# Servo_module.net
KiCad netlist of a schematic drawn in EasyEDA Pro
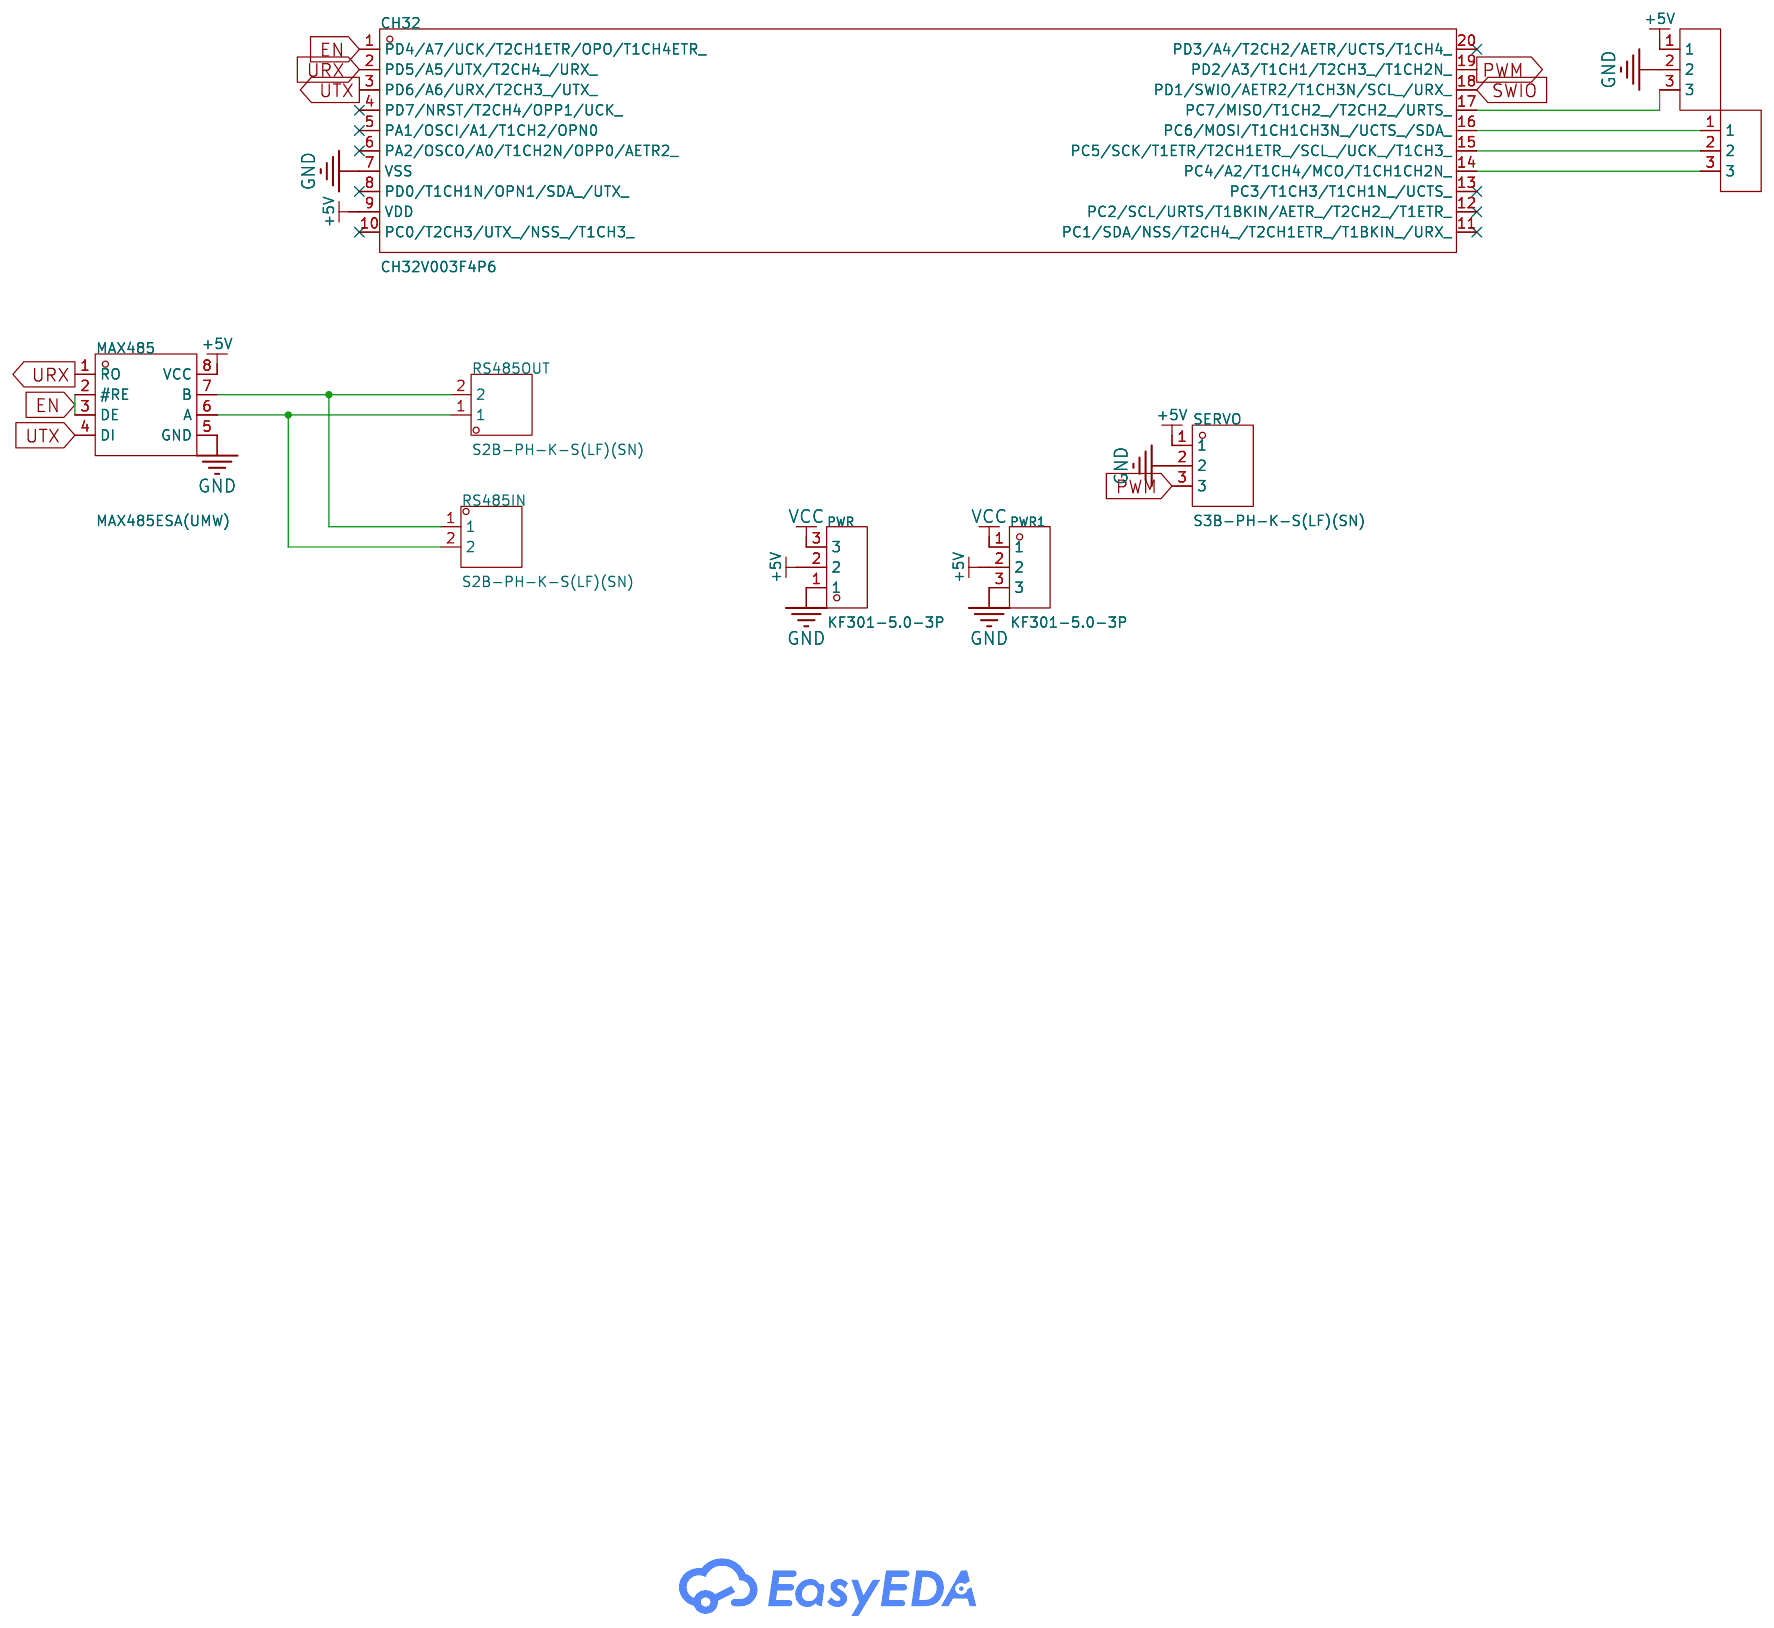
[diagram p0: schematic sheet]

(export (version "E")
  (design (tool "Eeschema 10.0.6"))
  (components
    (comp (ref "CH32")
      (value "CH32V003F4P6")
      (footprint "easyedapro:TSSOP-20_L6.5-W4.4-P0.65-LS6.4-BL")
      (fields (field (name "Manufacturer") "WCH(南京沁恒)"))
      (libsource (lib "easyedapro") (part "CH32V003F4P6"))
    )
    (comp (ref "H5")
      (value "~")
      (footprint "easyedapro:HDR-TH_3P-P2.54-V-M")
      (libsource (lib "easyedapro") (part "PZ254V-11-03P_C2937625"))
    )
    (comp (ref "H6")
      (value "~")
      (footprint "easyedapro:HDR-TH_3P-P2.54-V-M")
      (libsource (lib "easyedapro") (part "PZ254V-11-03P_C2937625"))
    )
    (comp (ref "MAX485")
      (value "MAX485ESA(UMW)")
      (footprint "easyedapro:SOP-8_L5.0-W4.0-P1.27-LS6.0-BL")
      (fields (field (name "Manufacturer") "UMW(友台半导体)"))
      (libsource (lib "easyedapro") (part "MAX485EAS"))
    )
    (comp (ref "PWR")
      (value "KF301-5.0-3P")
      (footprint "easyedapro:CONN-TH_3P-P5.00_KF301-5.0-3P")
      (fields (field (name "Manufacturer") "KEFA(科发)"))
      (libsource (lib "easyedapro") (part "KF301-5.0-3P"))
    )
    (comp (ref "PWR1")
      (value "KF301-5.0-3P")
      (footprint "easyedapro:CONN-TH_3P-P5.00_KF301-5.0-3P")
      (fields (field (name "Manufacturer") "KEFA(科发)"))
      (libsource (lib "easyedapro") (part "KF301-5.0-3P"))
    )
    (comp (ref "RS485IN")
      (value "S2B-PH-K-S(LF)(SN)")
      (footprint "easyedapro:CONN-TH_S2B-PH-K-S-LF-SN")
      (fields (field (name "Manufacturer") "JST"))
      (libsource (lib "easyedapro") (part "S2B-PH-K-S(LF)(SN)"))
    )
    (comp (ref "RS485OUT")
      (value "S2B-PH-K-S(LF)(SN)")
      (footprint "easyedapro:CONN-TH_S2B-PH-K-S-LF-SN")
      (fields (field (name "Manufacturer") "JST"))
      (libsource (lib "easyedapro") (part "S2B-PH-K-S(LF)(SN)"))
    )
    (comp (ref "SERVO")
      (value "S3B-PH-K-S(LF)(SN)")
      (footprint "easyedapro:CONN-TH_3P-P2.00_S3B-PH-K-S-LF-SN")
      (fields (field (name "Manufacturer") "JST"))
      (libsource (lib "easyedapro") (part "S3B-PH-K-S-(LF)(SN)"))
    )
  )
  (nets
    (net (code "1") (name "+5V") (class "Default")
      (node (ref "CH32") (pin "9") (pinfunction "VDD_9") (pintype "unspecified"))
      (node (ref "H5") (pin "1") (pinfunction "1_1") (pintype "unspecified"))
      (node (ref "MAX485") (pin "8") (pinfunction "VCC_8") (pintype "unspecified"))
      (node (ref "PWR") (pin "2") (pinfunction "2_2") (pintype "input"))
      (node (ref "PWR1") (pin "2") (pinfunction "2_2") (pintype "input"))
      (node (ref "SERVO") (pin "1") (pinfunction "1_1") (pintype "unspecified"))
    )
    (net (code "2") (name "EN") (class "Default")
      (node (ref "CH32") (pin "1") (pinfunction "PD4/A7/UCK/T2CH1ETR/OPO/T1CH4ETR__1") (pintype "unspecified"))
      (node (ref "MAX485") (pin "2") (pinfunction "#RE_2") (pintype "unspecified"))
      (node (ref "MAX485") (pin "3") (pinfunction "DE_3") (pintype "unspecified"))
    )
    (net (code "3") (name "GND") (class "Default")
      (node (ref "CH32") (pin "7") (pinfunction "VSS_7") (pintype "unspecified"))
      (node (ref "H5") (pin "2") (pinfunction "2_2") (pintype "unspecified"))
      (node (ref "MAX485") (pin "5") (pinfunction "GND_5") (pintype "unspecified"))
      (node (ref "PWR") (pin "1") (pinfunction "1_1") (pintype "input"))
      (node (ref "PWR1") (pin "3") (pinfunction "3_3") (pintype "input"))
      (node (ref "SERVO") (pin "2") (pinfunction "2_2") (pintype "unspecified"))
    )
    (net (code "4") (name "Net-(CH32-PC4{slash}A2{slash}T1CH4{slash}MCO{slash}T1CH1CH2N_)") (class "Default")
      (node (ref "CH32") (pin "14") (pinfunction "PC4/A2/T1CH4/MCO/T1CH1CH2N__14") (pintype "unspecified"))
      (node (ref "H6") (pin "3") (pinfunction "3_3") (pintype "unspecified"))
    )
    (net (code "5") (name "Net-(CH32-PC5{slash}SCK{slash}T1ETR{slash}T2CH1ETR_{slash}SCL_{slash}UCK_{slash}T1CH3_)") (class "Default")
      (node (ref "CH32") (pin "15") (pinfunction "PC5/SCK/T1ETR/T2CH1ETR_/SCL_/UCK_/T1CH3__15") (pintype "unspecified"))
      (node (ref "H6") (pin "2") (pinfunction "2_2") (pintype "unspecified"))
    )
    (net (code "6") (name "Net-(CH32-PC6{slash}MOSI{slash}T1CH1CH3N_{slash}UCTS_{slash}SDA_)") (class "Default")
      (node (ref "CH32") (pin "16") (pinfunction "PC6/MOSI/T1CH1CH3N_/UCTS_/SDA__16") (pintype "unspecified"))
      (node (ref "H6") (pin "1") (pinfunction "1_1") (pintype "unspecified"))
    )
    (net (code "7") (name "Net-(CH32-PC7{slash}MISO{slash}T1CH2_{slash}T2CH2_{slash}URTS_)") (class "Default")
      (node (ref "CH32") (pin "17") (pinfunction "PC7/MISO/T1CH2_/T2CH2_/URTS__17") (pintype "unspecified"))
      (node (ref "H5") (pin "3") (pinfunction "3_3") (pintype "unspecified"))
    )
    (net (code "8") (name "Net-(MAX485-A)") (class "Default")
      (node (ref "MAX485") (pin "6") (pinfunction "A_6") (pintype "unspecified"))
      (node (ref "RS485IN") (pin "2") (pinfunction "2_2") (pintype "unspecified"))
      (node (ref "RS485OUT") (pin "1") (pinfunction "1_1") (pintype "unspecified"))
    )
    (net (code "9") (name "Net-(MAX485-B)") (class "Default")
      (node (ref "MAX485") (pin "7") (pinfunction "B_7") (pintype "unspecified"))
      (node (ref "RS485IN") (pin "1") (pinfunction "1_1") (pintype "unspecified"))
      (node (ref "RS485OUT") (pin "2") (pinfunction "2_2") (pintype "unspecified"))
    )
    (net (code "10") (name "PWM") (class "Default")
      (node (ref "CH32") (pin "19") (pinfunction "PD2/A3/T1CH1/T2CH3_/T1CH2N__19") (pintype "unspecified"))
      (node (ref "SERVO") (pin "3") (pinfunction "3_3") (pintype "unspecified"))
    )
    (net (code "11") (name "SWIO") (class "Default")
      (node (ref "CH32") (pin "18") (pinfunction "PD1/SWIO/AETR2/T1CH3N/SCL_/URX__18") (pintype "unspecified"))
    )
    (net (code "12") (name "URX") (class "Default")
      (node (ref "CH32") (pin "2") (pinfunction "PD5/A5/UTX/T2CH4_/URX__2") (pintype "unspecified"))
      (node (ref "MAX485") (pin "1") (pinfunction "RO_1") (pintype "unspecified"))
    )
    (net (code "13") (name "UTX") (class "Default")
      (node (ref "CH32") (pin "3") (pinfunction "PD6/A6/URX/T2CH3_/UTX__3") (pintype "unspecified"))
      (node (ref "MAX485") (pin "4") (pinfunction "DI_4") (pintype "unspecified"))
    )
    (net (code "14") (name "VCC") (class "Default")
      (node (ref "PWR") (pin "3") (pinfunction "3_3") (pintype "input"))
      (node (ref "PWR1") (pin "1") (pinfunction "1_1") (pintype "input"))
    )
    (net (code "15") (name "unconnected-(CH32-PA1{slash}OSCI{slash}A1{slash}T1CH2{slash}OPN0-Pad5)") (class "Default")
      (node (ref "CH32") (pin "5") (pinfunction "PA1/OSCI/A1/T1CH2/OPN0_5") (pintype "unspecified+no_connect"))
    )
    (net (code "16") (name "unconnected-(CH32-PA2{slash}OSCO{slash}A0{slash}T1CH2N{slash}OPP0{slash}AETR2_-Pad6)") (class "Default")
      (node (ref "CH32") (pin "6") (pinfunction "PA2/OSCO/A0/T1CH2N/OPP0/AETR2__6") (pintype "unspecified+no_connect"))
    )
    (net (code "17") (name "unconnected-(CH32-PC0{slash}T2CH3{slash}UTX_{slash}NSS_{slash}T1CH3_-Pad10)") (class "Default")
      (node (ref "CH32") (pin "10") (pinfunction "PC0/T2CH3/UTX_/NSS_/T1CH3__10") (pintype "unspecified+no_connect"))
    )
    (net (code "18") (name "unconnected-(CH32-PC1{slash}SDA{slash}NSS{slash}T2CH4_{slash}T2CH1ETR_{slash}T1BKIN_{slash}URX_-Pad11)") (class "Default")
      (node (ref "CH32") (pin "11") (pinfunction "PC1/SDA/NSS/T2CH4_/T2CH1ETR_/T1BKIN_/URX__11") (pintype "unspecified+no_connect"))
    )
    (net (code "19") (name "unconnected-(CH32-PC2{slash}SCL{slash}URTS{slash}T1BKIN{slash}AETR_{slash}T2CH2_{slash}T1ETR_-Pad12)") (class "Default")
      (node (ref "CH32") (pin "12") (pinfunction "PC2/SCL/URTS/T1BKIN/AETR_/T2CH2_/T1ETR__12") (pintype "unspecified+no_connect"))
    )
    (net (code "20") (name "unconnected-(CH32-PC3{slash}T1CH3{slash}T1CH1N_{slash}UCTS_-Pad13)") (class "Default")
      (node (ref "CH32") (pin "13") (pinfunction "PC3/T1CH3/T1CH1N_/UCTS__13") (pintype "unspecified+no_connect"))
    )
    (net (code "21") (name "unconnected-(CH32-PD0{slash}T1CH1N{slash}OPN1{slash}SDA_{slash}UTX_-Pad8)") (class "Default")
      (node (ref "CH32") (pin "8") (pinfunction "PD0/T1CH1N/OPN1/SDA_/UTX__8") (pintype "unspecified+no_connect"))
    )
    (net (code "22") (name "unconnected-(CH32-PD3{slash}A4{slash}T2CH2{slash}AETR{slash}UCTS{slash}T1CH4_-Pad20)") (class "Default")
      (node (ref "CH32") (pin "20") (pinfunction "PD3/A4/T2CH2/AETR/UCTS/T1CH4__20") (pintype "unspecified+no_connect"))
    )
    (net (code "23") (name "unconnected-(CH32-PD7{slash}NRST{slash}T2CH4{slash}OPP1{slash}UCK_-Pad4)") (class "Default")
      (node (ref "CH32") (pin "4") (pinfunction "PD7/NRST/T2CH4/OPP1/UCK__4") (pintype "unspecified+no_connect"))
    )
  )
)
